# schema.net
KiCad netlist of a schematic drawn in EAGLE
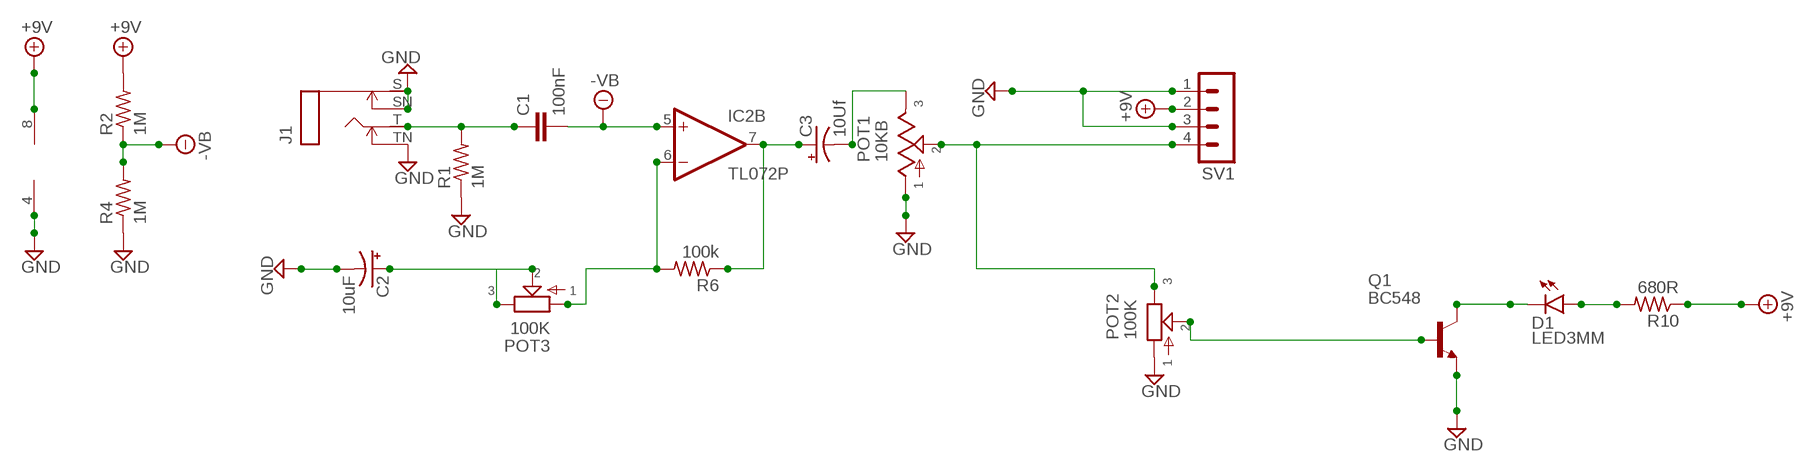
[diagram p0: schematic, sheet 1]

(export (version "E")
  (design (tool "Eeschema 10.0.6"))
  (components
    (comp (ref "C1")
      (value "100nF")
      (footprint "eagle-import:072X035")
      (libsource (lib "eagle-import") (part "072X0352"))
    )
    (comp (ref "C2")
      (value "10uF")
      (footprint "eagle-import:050_020_1")
      (libsource (lib "eagle-import") (part "0501"))
    )
    (comp (ref "C3")
      (value "10Uf")
      (footprint "eagle-import:050_020_1")
      (libsource (lib "eagle-import") (part "0501"))
    )
    (comp (ref "D1")
      (value "LED3MM")
      (footprint "eagle-import:LED3MM")
      (libsource (lib "eagle-import") (part "LED3MM"))
    )
    (comp (ref "IC2")
      (value "TL072P")
      (footprint "eagle-import:DIL08")
      (libsource (lib "eagle-import") (part "TL072P"))
    )
    (comp (ref "J1")
      (value "MONOSWS")
      (footprint "eagle-import:NMJ4HC-S")
      (libsource (lib "eagle-import") (part "MONOSWS"))
    )
    (comp (ref "POT1")
      (value "10KB")
      (footprint "eagle-import:16MM-PCB-MOUNT")
      (libsource (lib "eagle-import") (part "POTPCB"))
    )
    (comp (ref "POT2")
      (value "100K")
      (footprint "eagle-import:B25P")
      (libsource (lib "eagle-import") (part "POT-EU25"))
    )
    (comp (ref "POT3")
      (value "100K")
      (footprint "eagle-import:B25P")
      (libsource (lib "eagle-import") (part "POT-EU25"))
    )
    (comp (ref "Q1")
      (value "BC548")
      (footprint "eagle-import:TO92-EBC")
      (libsource (lib "eagle-import") (part "BC548"))
    )
    (comp (ref "R1")
      (value "1M")
      (footprint "eagle-import:R0207_3")
      (libsource (lib "eagle-import") (part "6MM.3"))
    )
    (comp (ref "R2")
      (value "1M")
      (footprint "eagle-import:R0207_3")
      (libsource (lib "eagle-import") (part "6MM.3"))
    )
    (comp (ref "R4")
      (value "1M")
      (footprint "eagle-import:R0207_3")
      (libsource (lib "eagle-import") (part "6MM.3"))
    )
    (comp (ref "R6")
      (value "100k")
      (footprint "eagle-import:R0207_1V")
      (libsource (lib "eagle-import") (part "6MM.1"))
    )
    (comp (ref "R10")
      (value "680R")
      (footprint "eagle-import:R0207_3")
      (libsource (lib "eagle-import") (part "6MM.3"))
    )
    (comp (ref "SV1")
      (value "MA04-1")
      (footprint "eagle-import:MA04-1")
      (libsource (lib "eagle-import") (part "MA04-1"))
    )
  )
  (nets
    (net (code "1") (name "+9V") (class "Default")
      (node (ref "IC2") (pin "8") (pinfunction "V+_8") (pintype "power_in"))
      (node (ref "R10") (pin "1") (pinfunction "1_1") (pintype "passive"))
      (node (ref "R2") (pin "2") (pinfunction "2_2") (pintype "passive"))
      (node (ref "SV1") (pin "2") (pinfunction "2_2") (pintype "passive"))
    )
    (net (code "2") (name "-VB") (class "Default")
      (node (ref "C1") (pin "2") (pinfunction "2_2") (pintype "passive"))
      (node (ref "IC2") (pin "5") (pinfunction "+IN_5") (pintype "input"))
      (node (ref "R2") (pin "1") (pinfunction "1_1") (pintype "passive"))
      (node (ref "R4") (pin "2") (pinfunction "2_2") (pintype "passive"))
    )
    (net (code "3") (name "GND") (class "Default")
      (node (ref "C2") (pin "-") (pinfunction "-_-") (pintype "passive"))
      (node (ref "IC2") (pin "4") (pinfunction "V-_4") (pintype "power_in"))
      (node (ref "J1") (pin "S") (pinfunction "S_S") (pintype "passive"))
      (node (ref "J1") (pin "SN") (pinfunction "SN_SN") (pintype "passive"))
      (node (ref "J1") (pin "TN") (pinfunction "TN_TN") (pintype "passive"))
      (node (ref "POT1") (pin "1") (pinfunction "1_1") (pintype "passive"))
      (node (ref "POT2") (pin "1") (pinfunction "1_1") (pintype "passive"))
      (node (ref "Q1") (pin "E") (pinfunction "E_E") (pintype "passive"))
      (node (ref "R1") (pin "1") (pinfunction "1_1") (pintype "passive"))
      (node (ref "R4") (pin "1") (pinfunction "1_1") (pintype "passive"))
      (node (ref "SV1") (pin "1") (pinfunction "1_1") (pintype "passive"))
      (node (ref "SV1") (pin "3") (pinfunction "3_3") (pintype "passive"))
    )
    (net (code "4") (name "Net-(C1-Pad1)") (class "Default")
      (node (ref "C1") (pin "1") (pinfunction "1_1") (pintype "passive"))
      (node (ref "J1") (pin "T") (pinfunction "T_T") (pintype "passive"))
      (node (ref "R1") (pin "2") (pinfunction "2_2") (pintype "passive"))
    )
    (net (code "5") (name "Net-(C2-Pad+)") (class "Default")
      (node (ref "C2") (pin "+") (pinfunction "+_+") (pintype "passive"))
      (node (ref "POT3") (pin "2") (pinfunction "2_2") (pintype "passive"))
      (node (ref "POT3") (pin "3") (pinfunction "3_3") (pintype "passive"))
    )
    (net (code "6") (name "Net-(C3-Pad-)") (class "Default")
      (node (ref "C3") (pin "-") (pinfunction "-_-") (pintype "passive"))
      (node (ref "POT1") (pin "3") (pinfunction "3_3") (pintype "passive"))
    )
    (net (code "7") (name "Net-(D1-C)") (class "Default")
      (node (ref "D1") (pin "K") (pinfunction "C_K") (pintype "passive"))
      (node (ref "Q1") (pin "C") (pinfunction "C_C") (pintype "passive"))
    )
    (net (code "8") (name "Net-(D1-PadA)") (class "Default")
      (node (ref "D1") (pin "A") (pinfunction "A_A") (pintype "passive"))
      (node (ref "R10") (pin "2") (pinfunction "2_2") (pintype "passive"))
    )
    (net (code "9") (name "Net-(IC2B--IN)") (class "Default")
      (node (ref "IC2") (pin "6") (pinfunction "-IN_6") (pintype "input"))
      (node (ref "POT3") (pin "1") (pinfunction "1_1") (pintype "passive"))
      (node (ref "R6") (pin "2") (pinfunction "2_2") (pintype "passive"))
    )
    (net (code "10") (name "Net-(IC2B-OUT)") (class "Default")
      (node (ref "C3") (pin "+") (pinfunction "+_+") (pintype "passive"))
      (node (ref "IC2") (pin "7") (pinfunction "OUT_7") (pintype "output"))
      (node (ref "R6") (pin "1") (pinfunction "1_1") (pintype "passive"))
    )
    (net (code "11") (name "Net-(POT1-Pad2)") (class "Default")
      (node (ref "POT1") (pin "2") (pinfunction "2_2") (pintype "passive"))
      (node (ref "POT2") (pin "3") (pinfunction "3_3") (pintype "passive"))
      (node (ref "SV1") (pin "4") (pinfunction "4_4") (pintype "passive"))
    )
    (net (code "12") (name "Net-(POT2-Pad2)") (class "Default")
      (node (ref "POT2") (pin "2") (pinfunction "2_2") (pintype "passive"))
      (node (ref "Q1") (pin "B") (pinfunction "B_B") (pintype "passive"))
    )
  )
)
